# IMU_connectors.net
KiCad netlist of a schematic drawn in EAGLE
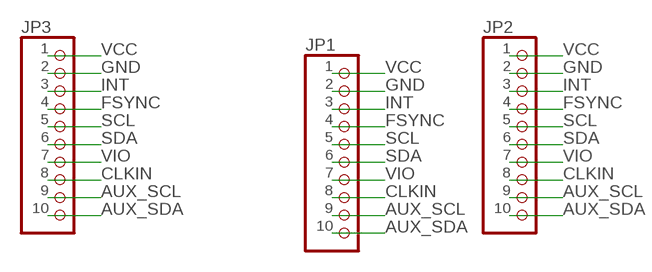
[diagram p0: schematic, sheet 1]

(export (version "E")
  (design (tool "Eeschema 10.0.6"))
  (components
    (comp (ref "JP1")
      (value "PINHD-1X10")
      (footprint "eagle-import:1X10")
      (libsource (lib "eagle-import") (part "PINHD-1X10"))
    )
    (comp (ref "JP2")
      (value "PINHD-1X10")
      (footprint "eagle-import:1X10")
      (libsource (lib "eagle-import") (part "PINHD-1X10"))
    )
    (comp (ref "JP3")
      (value "PINHD-1X10")
      (footprint "eagle-import:1X10")
      (libsource (lib "eagle-import") (part "PINHD-1X10"))
    )
  )
  (nets
    (net (code "1") (name "/AUX_SCL") (class "Default")
      (node (ref "JP1") (pin "9") (pinfunction "9_9") (pintype "passive"))
      (node (ref "JP2") (pin "9") (pinfunction "9_9") (pintype "passive"))
      (node (ref "JP3") (pin "9") (pinfunction "9_9") (pintype "passive"))
    )
    (net (code "2") (name "/AUX_SDA") (class "Default")
      (node (ref "JP1") (pin "10") (pinfunction "10_10") (pintype "passive"))
      (node (ref "JP2") (pin "10") (pinfunction "10_10") (pintype "passive"))
      (node (ref "JP3") (pin "10") (pinfunction "10_10") (pintype "passive"))
    )
    (net (code "3") (name "/CLKIN") (class "Default")
      (node (ref "JP1") (pin "8") (pinfunction "8_8") (pintype "passive"))
      (node (ref "JP2") (pin "8") (pinfunction "8_8") (pintype "passive"))
      (node (ref "JP3") (pin "8") (pinfunction "8_8") (pintype "passive"))
    )
    (net (code "4") (name "/FSYNC") (class "Default")
      (node (ref "JP1") (pin "4") (pinfunction "4_4") (pintype "passive"))
      (node (ref "JP2") (pin "4") (pinfunction "4_4") (pintype "passive"))
      (node (ref "JP3") (pin "4") (pinfunction "4_4") (pintype "passive"))
    )
    (net (code "5") (name "/GND") (class "Default")
      (node (ref "JP1") (pin "2") (pinfunction "2_2") (pintype "passive"))
      (node (ref "JP2") (pin "2") (pinfunction "2_2") (pintype "passive"))
      (node (ref "JP3") (pin "2") (pinfunction "2_2") (pintype "passive"))
    )
    (net (code "6") (name "/INT") (class "Default")
      (node (ref "JP1") (pin "3") (pinfunction "3_3") (pintype "passive"))
      (node (ref "JP2") (pin "3") (pinfunction "3_3") (pintype "passive"))
      (node (ref "JP3") (pin "3") (pinfunction "3_3") (pintype "passive"))
    )
    (net (code "7") (name "/SCL") (class "Default")
      (node (ref "JP1") (pin "5") (pinfunction "5_5") (pintype "passive"))
      (node (ref "JP2") (pin "5") (pinfunction "5_5") (pintype "passive"))
      (node (ref "JP3") (pin "5") (pinfunction "5_5") (pintype "passive"))
    )
    (net (code "8") (name "/SDA") (class "Default")
      (node (ref "JP1") (pin "6") (pinfunction "6_6") (pintype "passive"))
      (node (ref "JP2") (pin "6") (pinfunction "6_6") (pintype "passive"))
      (node (ref "JP3") (pin "6") (pinfunction "6_6") (pintype "passive"))
    )
    (net (code "9") (name "/VCC") (class "Default")
      (node (ref "JP1") (pin "1") (pinfunction "1_1") (pintype "passive"))
      (node (ref "JP2") (pin "1") (pinfunction "1_1") (pintype "passive"))
      (node (ref "JP3") (pin "1") (pinfunction "1_1") (pintype "passive"))
    )
    (net (code "10") (name "/VIO") (class "Default")
      (node (ref "JP1") (pin "7") (pinfunction "7_7") (pintype "passive"))
      (node (ref "JP2") (pin "7") (pinfunction "7_7") (pintype "passive"))
      (node (ref "JP3") (pin "7") (pinfunction "7_7") (pintype "passive"))
    )
  )
)
